# crass.net
KiCad netlist of a schematic drawn in EAGLE
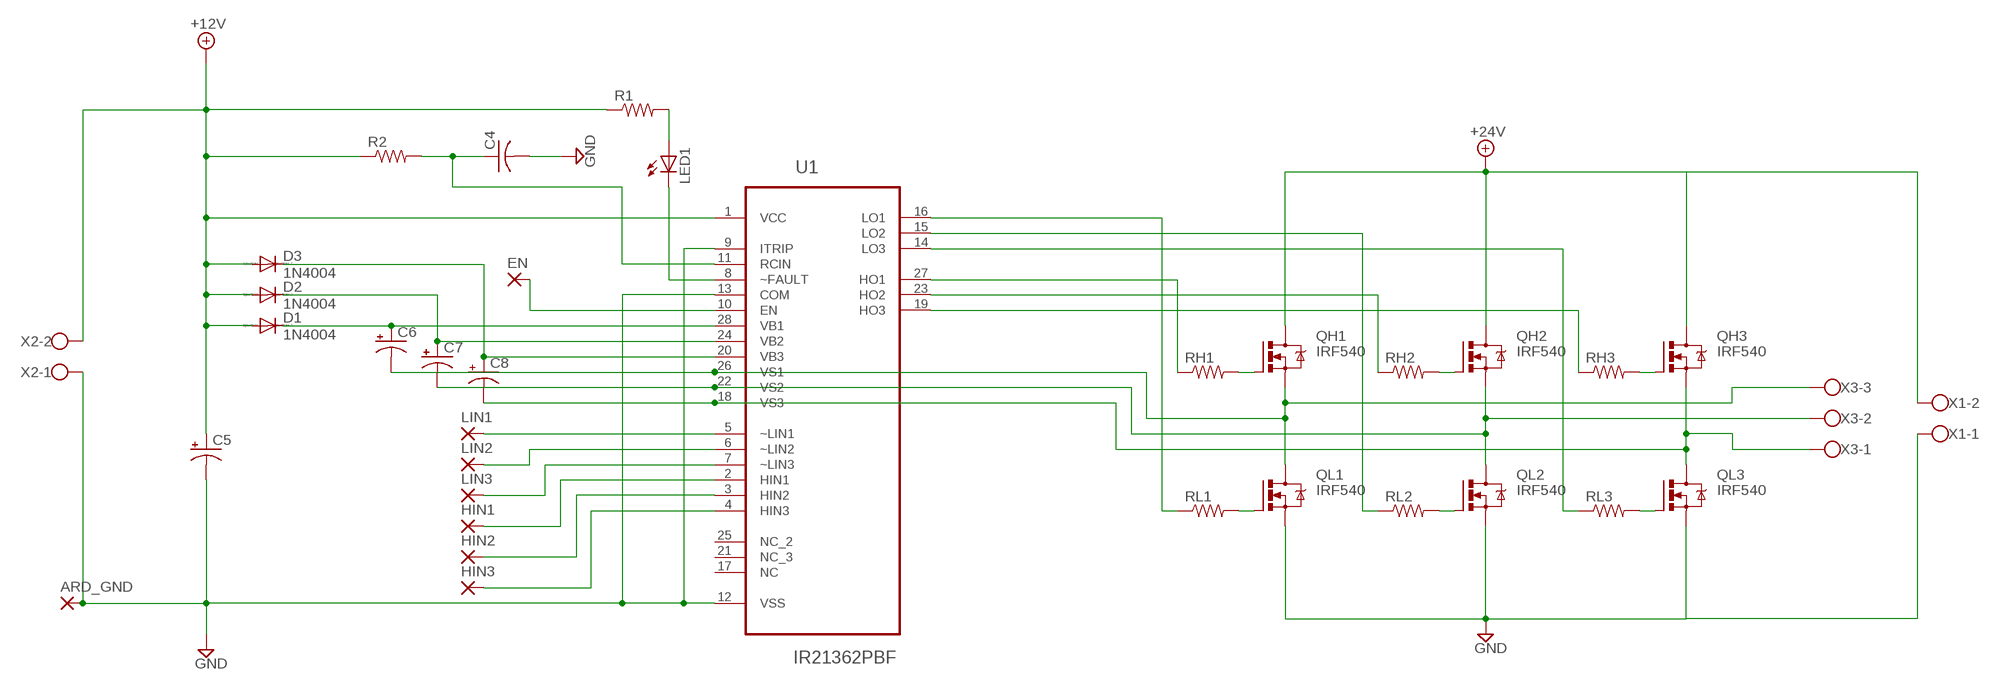
[diagram p0: schematic, sheet 1]

(export (version "E")
  (design (tool "Eeschema 10.0.6"))
  (components
    (comp (ref "ARD_GND")
      (value "2,54/1,0")
      (footprint "eagle-import:2,54_1,0")
      (libsource (lib "eagle-import") (part "2,54/1,0"))
    )
    (comp (ref "C4")
      (value "C-US025-025X050")
      (footprint "eagle-import:C025-025X050")
      (libsource (lib "eagle-import") (part "C-US025-025X050"))
    )
    (comp (ref "C5")
      (value "CPOL-USE2.5-7")
      (footprint "eagle-import:E2,5-7")
      (libsource (lib "eagle-import") (part "CPOL-USE2.5-7"))
    )
    (comp (ref "C6")
      (value "CPOL-USE2.5-5")
      (footprint "eagle-import:E2,5-5")
      (libsource (lib "eagle-import") (part "CPOL-USE2.5-5"))
    )
    (comp (ref "C7")
      (value "CPOL-USE2.5-5")
      (footprint "eagle-import:E2,5-5")
      (libsource (lib "eagle-import") (part "CPOL-USE2.5-5"))
    )
    (comp (ref "C8")
      (value "CPOL-USE2.5-5")
      (footprint "eagle-import:E2,5-5")
      (libsource (lib "eagle-import") (part "CPOL-USE2.5-5"))
    )
    (comp (ref "D1")
      (value "1N4004")
      (footprint "eagle-import:DO41-10")
      (libsource (lib "eagle-import") (part "1N4004"))
    )
    (comp (ref "D2")
      (value "1N4004")
      (footprint "eagle-import:DO41-10")
      (libsource (lib "eagle-import") (part "1N4004"))
    )
    (comp (ref "D3")
      (value "1N4004")
      (footprint "eagle-import:DO41-10")
      (libsource (lib "eagle-import") (part "1N4004"))
    )
    (comp (ref "EN")
      (value "2,54/1,0")
      (footprint "eagle-import:2,54_1,0")
      (libsource (lib "eagle-import") (part "2,54/1,0"))
    )
    (comp (ref "HIN1")
      (value "2,54/1,0")
      (footprint "eagle-import:2,54_1,0")
      (libsource (lib "eagle-import") (part "2,54/1,0"))
    )
    (comp (ref "HIN2")
      (value "2,54/1,0")
      (footprint "eagle-import:2,54_1,0")
      (libsource (lib "eagle-import") (part "2,54/1,0"))
    )
    (comp (ref "HIN3")
      (value "2,54/1,0")
      (footprint "eagle-import:2,54_1,0")
      (libsource (lib "eagle-import") (part "2,54/1,0"))
    )
    (comp (ref "LED1")
      (value "LED5MM")
      (footprint "eagle-import:LED5MM")
      (libsource (lib "eagle-import") (part "LED5MM"))
    )
    (comp (ref "LIN1")
      (value "2,54/1,0")
      (footprint "eagle-import:2,54_1,0")
      (libsource (lib "eagle-import") (part "2,54/1,0"))
    )
    (comp (ref "LIN2")
      (value "2,54/1,0")
      (footprint "eagle-import:2,54_1,0")
      (libsource (lib "eagle-import") (part "2,54/1,0"))
    )
    (comp (ref "LIN3")
      (value "2,54/1,0")
      (footprint "eagle-import:2,54_1,0")
      (libsource (lib "eagle-import") (part "2,54/1,0"))
    )
    (comp (ref "QH1")
      (value "IRF540")
      (footprint "eagle-import:TO220BV")
      (libsource (lib "eagle-import") (part "IRF540"))
    )
    (comp (ref "QH2")
      (value "IRF540")
      (footprint "eagle-import:TO220BV")
      (libsource (lib "eagle-import") (part "IRF540"))
    )
    (comp (ref "QH3")
      (value "IRF540")
      (footprint "eagle-import:TO220BV")
      (libsource (lib "eagle-import") (part "IRF540"))
    )
    (comp (ref "QL1")
      (value "IRF540")
      (footprint "eagle-import:TO220BV")
      (libsource (lib "eagle-import") (part "IRF540"))
    )
    (comp (ref "QL2")
      (value "IRF540")
      (footprint "eagle-import:TO220BV")
      (libsource (lib "eagle-import") (part "IRF540"))
    )
    (comp (ref "QL3")
      (value "IRF540")
      (footprint "eagle-import:TO220BV")
      (libsource (lib "eagle-import") (part "IRF540"))
    )
    (comp (ref "R1")
      (value "R-US_0204/7")
      (footprint "eagle-import:0204_7")
      (libsource (lib "eagle-import") (part "R-US_0204/7"))
    )
    (comp (ref "R2")
      (value "R-US_0204/7")
      (footprint "eagle-import:0204_7")
      (libsource (lib "eagle-import") (part "R-US_0204/7"))
    )
    (comp (ref "RH1")
      (value "R-US_0204/7")
      (footprint "eagle-import:0204_7")
      (libsource (lib "eagle-import") (part "R-US_0204/7"))
    )
    (comp (ref "RH2")
      (value "R-US_0204/7")
      (footprint "eagle-import:0204_7")
      (libsource (lib "eagle-import") (part "R-US_0204/7"))
    )
    (comp (ref "RH3")
      (value "R-US_0204/7")
      (footprint "eagle-import:0204_7")
      (libsource (lib "eagle-import") (part "R-US_0204/7"))
    )
    (comp (ref "RL1")
      (value "R-US_0204/7")
      (footprint "eagle-import:0204_7")
      (libsource (lib "eagle-import") (part "R-US_0204/7"))
    )
    (comp (ref "RL2")
      (value "R-US_0204/7")
      (footprint "eagle-import:0204_7")
      (libsource (lib "eagle-import") (part "R-US_0204/7"))
    )
    (comp (ref "RL3")
      (value "R-US_0204/7")
      (footprint "eagle-import:0204_7")
      (libsource (lib "eagle-import") (part "R-US_0204/7"))
    )
    (comp (ref "U1")
      (value "IR21362PBF")
      (footprint "eagle-import:DIP254P1524X635-28")
      (libsource (lib "eagle-import") (part "IR21362PBF"))
    )
    (comp (ref "X1")
      (value "W237-102")
      (footprint "eagle-import:W237-102")
      (fields (field (name "MPN") "237-102"))
      (libsource (lib "eagle-import") (part "W237-102"))
    )
    (comp (ref "X2")
      (value "W237-102")
      (footprint "eagle-import:W237-102")
      (fields (field (name "MPN") "237-102"))
      (libsource (lib "eagle-import") (part "W237-102"))
    )
    (comp (ref "X3")
      (value "W237-103")
      (footprint "eagle-import:W237-103")
      (fields (field (name "MPN") "237-103"))
      (libsource (lib "eagle-import") (part "W237-103"))
    )
  )
  (nets
    (net (code "1") (name "+12V") (class "Default")
      (node (ref "C5") (pin "+") (pinfunction "+_+") (pintype "passive"))
      (node (ref "D1") (pin "A") (pinfunction "A_A") (pintype "passive"))
      (node (ref "D2") (pin "A") (pinfunction "A_A") (pintype "passive"))
      (node (ref "D3") (pin "A") (pinfunction "A_A") (pintype "passive"))
      (node (ref "R1") (pin "1") (pinfunction "1_1") (pintype "passive"))
      (node (ref "R2") (pin "1") (pinfunction "1_1") (pintype "passive"))
      (node (ref "U1") (pin "1") (pinfunction "VCC_1") (pintype "power_in"))
      (node (ref "X2") (pin "2") (pinfunction "KL_2") (pintype "passive"))
    )
    (net (code "2") (name "+24V") (class "Default")
      (node (ref "QH1") (pin "D") (pinfunction "D_D") (pintype "passive"))
      (node (ref "QH2") (pin "D") (pinfunction "D_D") (pintype "passive"))
      (node (ref "QH3") (pin "D") (pinfunction "D_D") (pintype "passive"))
      (node (ref "X1") (pin "2") (pinfunction "KL_2") (pintype "passive"))
    )
    (net (code "3") (name "GND") (class "Default")
      (node (ref "ARD_GND") (pin "1") (pinfunction "P_1") (pintype "passive"))
      (node (ref "C4") (pin "2") (pinfunction "2_2") (pintype "passive"))
      (node (ref "C5") (pin "-") (pinfunction "-_-") (pintype "passive"))
      (node (ref "QL1") (pin "S") (pinfunction "S_S") (pintype "passive"))
      (node (ref "QL2") (pin "S") (pinfunction "S_S") (pintype "passive"))
      (node (ref "QL3") (pin "S") (pinfunction "S_S") (pintype "passive"))
      (node (ref "U1") (pin "12") (pinfunction "VSS_12") (pintype "power_in"))
      (node (ref "U1") (pin "13") (pinfunction "COM_13") (pintype "input"))
      (node (ref "U1") (pin "9") (pinfunction "ITRIP_9") (pintype "input"))
      (node (ref "X1") (pin "1") (pinfunction "KL_1") (pintype "passive"))
      (node (ref "X2") (pin "1") (pinfunction "KL_1") (pintype "passive"))
    )
    (net (code "4") (name "Net-(EN-P)") (class "Default")
      (node (ref "EN") (pin "1") (pinfunction "P_1") (pintype "passive"))
      (node (ref "U1") (pin "10") (pinfunction "EN_10") (pintype "input"))
    )
    (net (code "5") (name "Net-(HIN1-P)") (class "Default")
      (node (ref "HIN1") (pin "1") (pinfunction "P_1") (pintype "passive"))
      (node (ref "U1") (pin "2") (pinfunction "HIN1_2") (pintype "input"))
    )
    (net (code "6") (name "Net-(HIN2-P)") (class "Default")
      (node (ref "HIN2") (pin "1") (pinfunction "P_1") (pintype "passive"))
      (node (ref "U1") (pin "3") (pinfunction "HIN2_3") (pintype "input"))
    )
    (net (code "7") (name "Net-(HIN3-P)") (class "Default")
      (node (ref "HIN3") (pin "1") (pinfunction "P_1") (pintype "passive"))
      (node (ref "U1") (pin "4") (pinfunction "HIN3_4") (pintype "input"))
    )
    (net (code "8") (name "Net-(LED1-C)") (class "Default")
      (node (ref "LED1") (pin "K") (pinfunction "C_K") (pintype "passive"))
      (node (ref "U1") (pin "8") (pinfunction "~{FAULT}_8") (pintype "input"))
    )
    (net (code "9") (name "Net-(LED1-PadA)") (class "Default")
      (node (ref "LED1") (pin "A") (pinfunction "A_A") (pintype "passive"))
      (node (ref "R1") (pin "2") (pinfunction "2_2") (pintype "passive"))
    )
    (net (code "10") (name "Net-(LIN1-P)") (class "Default")
      (node (ref "LIN1") (pin "1") (pinfunction "P_1") (pintype "passive"))
      (node (ref "U1") (pin "5") (pinfunction "~{LIN1}_5") (pintype "input"))
    )
    (net (code "11") (name "Net-(LIN2-P)") (class "Default")
      (node (ref "LIN2") (pin "1") (pinfunction "P_1") (pintype "passive"))
      (node (ref "U1") (pin "6") (pinfunction "~{LIN2}_6") (pintype "input"))
    )
    (net (code "12") (name "Net-(LIN3-P)") (class "Default")
      (node (ref "LIN3") (pin "1") (pinfunction "P_1") (pintype "passive"))
      (node (ref "U1") (pin "7") (pinfunction "~{LIN3}_7") (pintype "input"))
    )
    (net (code "13") (name "Net-(QH1-PadG)") (class "Default")
      (node (ref "QH1") (pin "G") (pinfunction "G_G") (pintype "passive"))
      (node (ref "RH1") (pin "2") (pinfunction "2_2") (pintype "passive"))
    )
    (net (code "14") (name "Net-(QH2-PadG)") (class "Default")
      (node (ref "QH2") (pin "G") (pinfunction "G_G") (pintype "passive"))
      (node (ref "RH2") (pin "2") (pinfunction "2_2") (pintype "passive"))
    )
    (net (code "15") (name "Net-(QH3-PadG)") (class "Default")
      (node (ref "QH3") (pin "G") (pinfunction "G_G") (pintype "passive"))
      (node (ref "RH3") (pin "2") (pinfunction "2_2") (pintype "passive"))
    )
    (net (code "16") (name "Net-(QL1-PadG)") (class "Default")
      (node (ref "QL1") (pin "G") (pinfunction "G_G") (pintype "passive"))
      (node (ref "RL1") (pin "2") (pinfunction "2_2") (pintype "passive"))
    )
    (net (code "17") (name "Net-(QL2-PadG)") (class "Default")
      (node (ref "QL2") (pin "G") (pinfunction "G_G") (pintype "passive"))
      (node (ref "RL2") (pin "2") (pinfunction "2_2") (pintype "passive"))
    )
    (net (code "18") (name "Net-(QL3-PadG)") (class "Default")
      (node (ref "QL3") (pin "G") (pinfunction "G_G") (pintype "passive"))
      (node (ref "RL3") (pin "2") (pinfunction "2_2") (pintype "passive"))
    )
    (net (code "19") (name "Net-(U1-HO1)") (class "Default")
      (node (ref "RH1") (pin "1") (pinfunction "1_1") (pintype "passive"))
      (node (ref "U1") (pin "27") (pinfunction "HO1_27") (pintype "output"))
    )
    (net (code "20") (name "Net-(U1-HO2)") (class "Default")
      (node (ref "RH2") (pin "1") (pinfunction "1_1") (pintype "passive"))
      (node (ref "U1") (pin "23") (pinfunction "HO2_23") (pintype "output"))
    )
    (net (code "21") (name "Net-(U1-HO3)") (class "Default")
      (node (ref "RH3") (pin "1") (pinfunction "1_1") (pintype "passive"))
      (node (ref "U1") (pin "19") (pinfunction "HO3_19") (pintype "output"))
    )
    (net (code "22") (name "Net-(U1-LO1)") (class "Default")
      (node (ref "RL1") (pin "1") (pinfunction "1_1") (pintype "passive"))
      (node (ref "U1") (pin "16") (pinfunction "LO1_16") (pintype "output"))
    )
    (net (code "23") (name "Net-(U1-LO2)") (class "Default")
      (node (ref "RL2") (pin "1") (pinfunction "1_1") (pintype "passive"))
      (node (ref "U1") (pin "15") (pinfunction "LO2_15") (pintype "output"))
    )
    (net (code "24") (name "Net-(U1-LO3)") (class "Default")
      (node (ref "RL3") (pin "1") (pinfunction "1_1") (pintype "passive"))
      (node (ref "U1") (pin "14") (pinfunction "LO3_14") (pintype "output"))
    )
    (net (code "25") (name "Net-(U1-RCIN)") (class "Default")
      (node (ref "C4") (pin "1") (pinfunction "1_1") (pintype "passive"))
      (node (ref "R2") (pin "2") (pinfunction "2_2") (pintype "passive"))
      (node (ref "U1") (pin "11") (pinfunction "RCIN_11") (pintype "input"))
    )
    (net (code "26") (name "Net-(U1-VB1)") (class "Default")
      (node (ref "C6") (pin "+") (pinfunction "+_+") (pintype "passive"))
      (node (ref "D1") (pin "C") (pinfunction "C_C") (pintype "passive"))
      (node (ref "U1") (pin "28") (pinfunction "VB1_28") (pintype "power_in"))
    )
    (net (code "27") (name "Net-(U1-VB2)") (class "Default")
      (node (ref "C7") (pin "+") (pinfunction "+_+") (pintype "passive"))
      (node (ref "D2") (pin "C") (pinfunction "C_C") (pintype "passive"))
      (node (ref "U1") (pin "24") (pinfunction "VB2_24") (pintype "input"))
    )
    (net (code "28") (name "Net-(U1-VB3)") (class "Default")
      (node (ref "C8") (pin "+") (pinfunction "+_+") (pintype "passive"))
      (node (ref "D3") (pin "C") (pinfunction "C_C") (pintype "passive"))
      (node (ref "U1") (pin "20") (pinfunction "VB3_20") (pintype "input"))
    )
    (net (code "29") (name "Net-(U1-VS1)") (class "Default")
      (node (ref "C6") (pin "-") (pinfunction "-_-") (pintype "passive"))
      (node (ref "QH1") (pin "S") (pinfunction "S_S") (pintype "passive"))
      (node (ref "QL1") (pin "D") (pinfunction "D_D") (pintype "passive"))
      (node (ref "U1") (pin "26") (pinfunction "VS1_26") (pintype "power_in"))
      (node (ref "X3") (pin "3") (pinfunction "KL_3") (pintype "passive"))
    )
    (net (code "30") (name "Net-(U1-VS2)") (class "Default")
      (node (ref "C7") (pin "-") (pinfunction "-_-") (pintype "passive"))
      (node (ref "QH2") (pin "S") (pinfunction "S_S") (pintype "passive"))
      (node (ref "QL2") (pin "D") (pinfunction "D_D") (pintype "passive"))
      (node (ref "U1") (pin "22") (pinfunction "VS2_22") (pintype "power_in"))
      (node (ref "X3") (pin "2") (pinfunction "KL_2") (pintype "passive"))
    )
    (net (code "31") (name "Net-(U1-VS3)") (class "Default")
      (node (ref "C8") (pin "-") (pinfunction "-_-") (pintype "passive"))
      (node (ref "QH3") (pin "S") (pinfunction "S_S") (pintype "passive"))
      (node (ref "QL3") (pin "D") (pinfunction "D_D") (pintype "passive"))
      (node (ref "U1") (pin "18") (pinfunction "VS3_18") (pintype "power_in"))
      (node (ref "X3") (pin "1") (pinfunction "KL_1") (pintype "passive"))
    )
    (net (code "32") (name "unconnected-(U1-NC-Pad17)") (class "Default")
      (node (ref "U1") (pin "17") (pinfunction "NC_17") (pintype "no_connect"))
    )
    (net (code "33") (name "unconnected-(U1-NC_2-Pad25)") (class "Default")
      (node (ref "U1") (pin "25") (pinfunction "NC_2_25") (pintype "no_connect"))
    )
    (net (code "34") (name "unconnected-(U1-NC_3-Pad21)") (class "Default")
      (node (ref "U1") (pin "21") (pinfunction "NC_3_21") (pintype "no_connect"))
    )
  )
)
